# main.net
KiCad netlist of a schematic drawn in Altium Designer
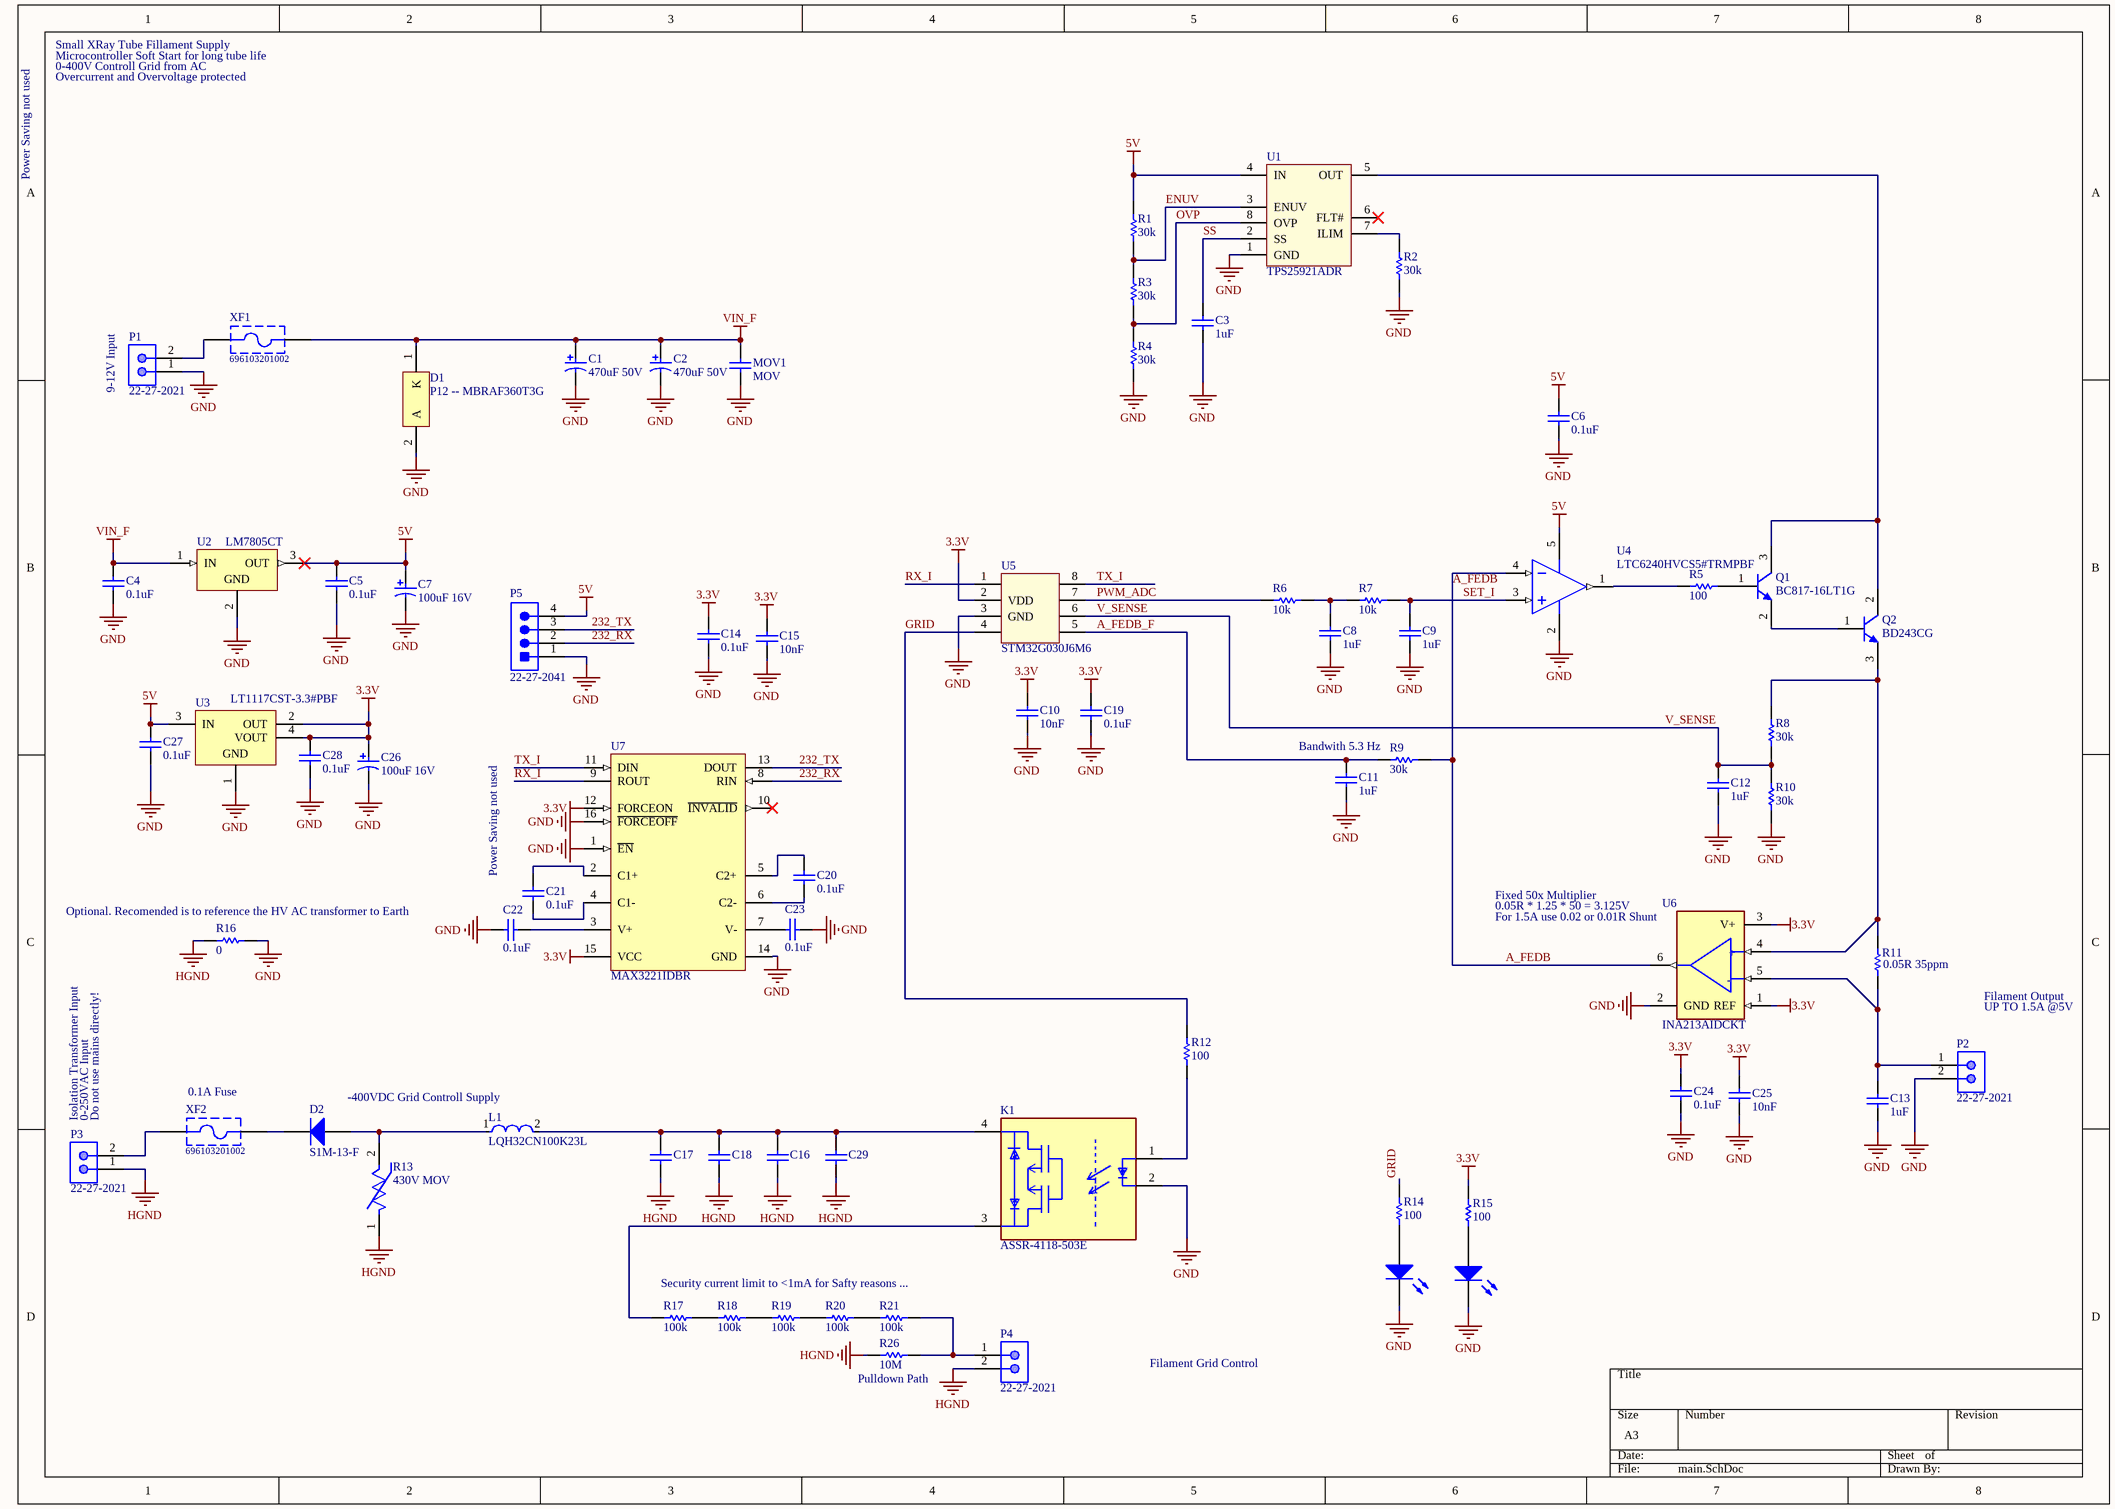
[diagram p0: main.SchDoc]

(export (version "E")
  (design (tool "Eeschema 10.0.6"))
  (components
    (comp (ref "C1")
      (value "470uF 50V")
      (footprint "PNSC-CAP-10x20-P2")
      (description "Aluminum Electrolytic Capacitor, 470 uF, +/- 20%, 50 V, -55 to 105 degC, 2-Pin THD, RoHS, Bulk")
      (fields (field (name "MANUFACTURER") "Panasonic"))
      (libsource (lib "Altium Content Vault") (part "CAP-P-2"))
    )
    (comp (ref "C2")
      (value "470uF 50V")
      (footprint "PNSC-CAP-10x20-P2")
      (description "Aluminum Electrolytic Capacitor, 470 uF, +/- 20%, 50 V, -55 to 105 degC, 2-Pin THD, RoHS, Bulk")
      (fields (field (name "MANUFACTURER") "Panasonic"))
      (libsource (lib "Altium Content Vault") (part "CAP-P-2"))
    )
    (comp (ref "C3")
      (value "1uF")
      (footprint "CAPC2013X145X50LL20T25")
      (fields (field (name "MANUFACTURER") "Kemet") (field (name "PART NUMBER") "C0805C105K4PACTU"))
      (libsource (lib "Altium Content Vault") (part "CAP"))
    )
    (comp (ref "C4")
      (value "0.1uF")
      (footprint "CAPC2013X145X50LL20T25")
      (fields (field (name "MANUFACTURER") "Kemet") (field (name "PART NUMBER") "C0805C105K4PACTU"))
      (libsource (lib "Altium Content Vault") (part "CAP"))
    )
    (comp (ref "C5")
      (value "0.1uF")
      (footprint "CAPC2013X145X50LL20T25")
      (fields (field (name "MANUFACTURER") "Kemet") (field (name "PART NUMBER") "C0805C105K4PACTU"))
      (libsource (lib "Altium Content Vault") (part "CAP"))
    )
    (comp (ref "C6")
      (value "0.1uF")
      (footprint "CAPC2013X145X50LL20T25")
      (fields (field (name "MANUFACTURER") "Kemet") (field (name "PART NUMBER") "C0805C105K4PACTU"))
      (libsource (lib "Altium Content Vault") (part "CAP"))
    )
    (comp (ref "C7")
      (value "100uF 16V")
      (footprint "CAPPR55-250-1120X630X1220")
      (fields (field (name "MANUFACTURER") "Panasonic"))
      (libsource (lib "Altium Content Vault") (part "CAP-P-2"))
    )
    (comp (ref "C8")
      (value "1uF")
      (footprint "CAPC2013X145X50LL20T25")
      (fields (field (name "MANUFACTURER") "Kemet") (field (name "PART NUMBER") "C0805C105K4PACTU"))
      (libsource (lib "Altium Content Vault") (part "CAP"))
    )
    (comp (ref "C9")
      (value "1uF")
      (footprint "CAPC2013X145X50LL20T25")
      (fields (field (name "MANUFACTURER") "Kemet") (field (name "PART NUMBER") "C0805C105K4PACTU"))
      (libsource (lib "Altium Content Vault") (part "CAP"))
    )
    (comp (ref "C10")
      (value "10nF")
      (footprint "CAPC2013X145X50LL20T25")
      (fields (field (name "MANUFACTURER") "Kemet") (field (name "PART NUMBER") "C0805C105K4PACTU"))
      (libsource (lib "Altium Content Vault") (part "CAP"))
    )
    (comp (ref "C11")
      (value "1uF")
      (footprint "CAPC2013X145X50LL20T25")
      (fields (field (name "MANUFACTURER") "Kemet") (field (name "PART NUMBER") "C0805C105K4PACTU"))
      (libsource (lib "Altium Content Vault") (part "CAP"))
    )
    (comp (ref "C12")
      (value "1uF")
      (footprint "CAPC2013X145X50LL20T25")
      (fields (field (name "MANUFACTURER") "Kemet") (field (name "PART NUMBER") "C0805C105K4PACTU"))
      (libsource (lib "Altium Content Vault") (part "CAP"))
    )
    (comp (ref "C13")
      (value "1uF")
      (footprint "CAPC2013X145X50LL20T25")
      (fields (field (name "MANUFACTURER") "Kemet") (field (name "PART NUMBER") "C0805C105K4PACTU"))
      (libsource (lib "Altium Content Vault") (part "CAP"))
    )
    (comp (ref "C14")
      (value "0.1uF")
      (footprint "CAPC2013X145X50LL20T25")
      (fields (field (name "MANUFACTURER") "Kemet") (field (name "PART NUMBER") "C0805C105K4PACTU"))
      (libsource (lib "Altium Content Vault") (part "CAP"))
    )
    (comp (ref "C15")
      (value "10nF")
      (footprint "CAPC2013X145X50LL20T25")
      (fields (field (name "MANUFACTURER") "Kemet") (field (name "PART NUMBER") "C0805C105K4PACTU"))
      (libsource (lib "Altium Content Vault") (part "CAP"))
    )
    (comp (ref "C16")
      (value "20uF 50V X7R")
      (footprint "CAPC3216X180X50LL20T30")
      (description "HighVoltaeCaps")
      (fields (field (name "MANUFACTURER") "Samsung Electro-Mechanics"))
      (libsource (lib "Altium Content Vault") (part "CAP-NP-2"))
    )
    (comp (ref "C17")
      (value "20uF 50V X7R")
      (footprint "CAPC3216X180X50LL20T30")
      (description "HighVoltaeCaps")
      (fields (field (name "MANUFACTURER") "Samsung Electro-Mechanics"))
      (libsource (lib "Altium Content Vault") (part "CAP-NP-2"))
    )
    (comp (ref "C18")
      (value "20uF 50V X7R")
      (footprint "CAPC3216X180X50LL20T30")
      (description "HighVoltaeCaps")
      (fields (field (name "MANUFACTURER") "Samsung Electro-Mechanics"))
      (libsource (lib "Altium Content Vault") (part "CAP-NP-2"))
    )
    (comp (ref "C19")
      (value "0.1uF")
      (footprint "CAPC2013X145X50LL20T25")
      (fields (field (name "MANUFACTURER") "Kemet") (field (name "PART NUMBER") "C0805C105K4PACTU"))
      (libsource (lib "Altium Content Vault") (part "CAP"))
    )
    (comp (ref "C20")
      (value "0.1uF")
      (footprint "CAPC2013X145X50LL20T25")
      (fields (field (name "MANUFACTURER") "Kemet") (field (name "PART NUMBER") "C0805C105K4PACTU"))
      (libsource (lib "Altium Content Vault") (part "CAP"))
    )
    (comp (ref "C21")
      (value "0.1uF")
      (footprint "CAPC2013X145X50LL20T25")
      (fields (field (name "MANUFACTURER") "Kemet") (field (name "PART NUMBER") "C0805C105K4PACTU"))
      (libsource (lib "Altium Content Vault") (part "CAP"))
    )
    (comp (ref "C22")
      (value "0.1uF")
      (footprint "CAPC2013X145X50LL20T25")
      (fields (field (name "MANUFACTURER") "Kemet") (field (name "PART NUMBER") "C0805C105K4PACTU"))
      (libsource (lib "Altium Content Vault") (part "CAP"))
    )
    (comp (ref "C23")
      (value "0.1uF")
      (footprint "CAPC2013X145X50LL20T25")
      (fields (field (name "MANUFACTURER") "Kemet") (field (name "PART NUMBER") "C0805C105K4PACTU"))
      (libsource (lib "Altium Content Vault") (part "CAP"))
    )
    (comp (ref "C24")
      (value "0.1uF")
      (footprint "CAPC2013X145X50LL20T25")
      (fields (field (name "MANUFACTURER") "Kemet") (field (name "PART NUMBER") "C0805C105K4PACTU"))
      (libsource (lib "Altium Content Vault") (part "CAP"))
    )
    (comp (ref "C25")
      (value "10nF")
      (footprint "CAPC2013X145X50LL20T25")
      (fields (field (name "MANUFACTURER") "Kemet") (field (name "PART NUMBER") "C0805C105K4PACTU"))
      (libsource (lib "Altium Content Vault") (part "CAP"))
    )
    (comp (ref "C26")
      (value "100uF 16V")
      (footprint "CAPPR55-250-1120X630X1220")
      (fields (field (name "MANUFACTURER") "Panasonic"))
      (libsource (lib "Altium Content Vault") (part "CAP-P-2"))
    )
    (comp (ref "C27")
      (value "0.1uF")
      (footprint "CAPC2013X145X50LL20T25")
      (fields (field (name "MANUFACTURER") "Kemet") (field (name "PART NUMBER") "C0805C105K4PACTU"))
      (libsource (lib "Altium Content Vault") (part "CAP"))
    )
    (comp (ref "C28")
      (value "0.1uF")
      (footprint "CAPC2013X145X50LL20T25")
      (fields (field (name "MANUFACTURER") "Kemet") (field (name "PART NUMBER") "C0805C105K4PACTU"))
      (libsource (lib "Altium Content Vault") (part "CAP"))
    )
    (comp (ref "C29")
      (value "20uF 50V X7R")
      (footprint "CAPC3216X180X50LL20T30")
      (description "HighVoltaeCaps")
      (fields (field (name "MANUFACTURER") "Samsung Electro-Mechanics"))
      (libsource (lib "Altium Content Vault") (part "CAP-NP-2"))
    )
    (comp (ref "D1")
      (value "P12 -- MBRAF360T3G")
      (footprint "ONSC-SMA-FL-2-403AA-01_V")
      (description "P12 -- Schottky Power Rectifier, 2-Pin SMA, Pb-Free, Tape and Reel")
      (fields (field (name "PARTNUMBER") "MBRAF360T3G") (field (name "MANUFACTURER") "On Semiconductor"))
      (libsource (lib "Altium Content Vault") (part "ONSC-D-K1A2-2_A"))
    )
    (comp (ref "D2")
      (value "S1M-13-F")
      (footprint "DIOD-S1M-13-F-SMA-2_V")
      (fields (field (name "MANUFACTURER") "Diodes Inc"))
      (libsource (lib "Altium Content Vault") (part "DIOD-D-A1K2-2"))
    )
    (comp (ref "K1")
      (value "ASSR-4118-503E")
      (footprint "FP-SO-4-MFG")
      (description "SSR RELAY SPST-NO 100MA 0-400V")
      (fields
        (field (name "OCTOPART") "https://octopart.com/assr-1218-503e-broadcom-71127361")
        (field (name "MANUFACTURER") "Broadcom")
      )
      (libsource (lib "Altium Content Vault") (part "ad51281b5d02327e8cabe319bebe261"))
    )
    (comp (ref "L1")
      (value "LQH32CN100K23L")
      (footprint "FP-LQH32CN100K23L-MFG")
      (description "FIXED IND 10UH 300MA 440 MOHM")
      (fields (field (name "TOLERANCE") "10%") (field (name "MANUFACTURER") "Murata"))
      (libsource (lib "Altium Content Vault") (part "725321dda6339637d4d059423bc1c3c"))
    )
    (comp (ref "LED1")
      (value "LED")
      (footprint "0805_A")
      (description "SMD mono-color Chip LED, WL-SMCW, Super Red")
      (fields (field (name "MANUFACTURER") "Wuerth Elektronik") (field (name "PARTNUMBER") "150080SS75000"))
      (libsource (lib "Altium Content Vault") (part "WE-LED_K1A2-2"))
    )
    (comp (ref "LED2")
      (value "LED")
      (footprint "0805_A")
      (description "SMD mono-color Chip LED, WL-SMCW, Super Red")
      (fields (field (name "MANUFACTURER") "Wuerth Elektronik") (field (name "PARTNUMBER") "150080SS75000"))
      (libsource (lib "Altium Content Vault") (part "WE-LED_K1A2-2"))
    )
    (comp (ref "MOV1")
      (value "MOV")
      (footprint "CAPC1206(3216)100_N")
      (fields (field (name "TOLERANCE") "Â±10%"))
      (libsource (lib "Altium Content Vault") (part "CAP"))
    )
    (comp (ref "P1")
      (value "22-27-2021")
      (footprint "MOLX-22-27-2021_V")
      (fields (field (name "MANUFACTURER") "Molex") (field (name "PARTNUMBER") "0022272021"))
      (libsource (lib "Altium Content Vault") (part "CN-1P-M-R2"))
    )
    (comp (ref "P2")
      (value "22-27-2021")
      (footprint "MOLX-22-27-2021_V")
      (fields (field (name "MANUFACTURER") "Molex") (field (name "PARTNUMBER") "0022272021"))
      (libsource (lib "") (part "CN-1P-M-R2_1"))
    )
    (comp (ref "P3")
      (value "22-27-2021")
      (footprint "MOLX-22-27-2021_V")
      (fields (field (name "MANUFACTURER") "Molex") (field (name "PARTNUMBER") "0022272021"))
      (libsource (lib "Altium Content Vault") (part "CN-1P-M-R2"))
    )
    (comp (ref "P4")
      (value "22-27-2021")
      (footprint "MOLX-22-27-2021_V")
      (fields (field (name "MANUFACTURER") "Molex") (field (name "PARTNUMBER") "0022272021"))
      (libsource (lib "") (part "CN-1P-M-R2_1"))
    )
    (comp (ref "P5")
      (value "22-27-2041")
      (footprint "MOLX-22-27-2041_V")
      (description "Male Header, Pitch 2.54 mm, 1 x 4 Position, Height 11.7 mm, Tail Length 3.56 mm, RoHS, Bulk")
      (fields (field (name "MANUFACTURER") "Molex"))
      (libsource (lib "Altium Content Vault") (part "CN-1P-M-R4"))
    )
    (comp (ref "Q1")
      (value "BC817-16LT1G")
      (footprint "ONSC-SOT-23-3-318-08_V")
      (description "General Purpose Transistor, NPN Silicon, 3-Pin SOT-23, Pb-Free, Tape and Reel")
      (fields (field (name "MANUFACTURER") "On Semiconductor"))
      (libsource (lib "Altium Content Vault") (part "ONSC-NPN-B1E2C3-3"))
    )
    (comp (ref "Q2")
      (value "BD243CG")
      (footprint "ONSC-TO-220-3-221A-09")
      (description "Complementary Silicon Plastic Power Transistor, 3-Pin TO-220, Pb-Free, Tube")
      (fields (field (name "MANUFACTURER") "On Semiconductor"))
      (libsource (lib "Altium Content Vault") (part "ONSC-NPN-B1C2E3-3_C"))
    )
    (comp (ref "R1")
      (value "30k")
      (footprint "RESC2013X60X40NL20T25")
      (fields (field (name "MANUFACTURER") "Panasonic") (field (name "PART NUMBER") "ERA-6AEB303V"))
      (libsource (lib "Altium Content Vault") (part "RES"))
    )
    (comp (ref "R2")
      (value "30k")
      (footprint "RESC2013X60X40NL20T25")
      (fields (field (name "MANUFACTURER") "Panasonic") (field (name "PART NUMBER") "ERA-6AEB303V"))
      (libsource (lib "Altium Content Vault") (part "RES"))
    )
    (comp (ref "R3")
      (value "30k")
      (footprint "RESC2013X60X40NL20T25")
      (fields (field (name "MANUFACTURER") "Panasonic") (field (name "PART NUMBER") "ERA-6AEB303V"))
      (libsource (lib "Altium Content Vault") (part "RES"))
    )
    (comp (ref "R4")
      (value "30k")
      (footprint "RESC2013X60X40NL20T25")
      (fields (field (name "MANUFACTURER") "Panasonic") (field (name "PART NUMBER") "ERA-6AEB303V"))
      (libsource (lib "Altium Content Vault") (part "RES"))
    )
    (comp (ref "R5")
      (value "100")
      (footprint "RESC2013X60X40NL20T25")
      (fields (field (name "MANUFACTURER") "Panasonic") (field (name "PART NUMBER") "ERA-6AEB303V"))
      (libsource (lib "Altium Content Vault") (part "RES"))
    )
    (comp (ref "R6")
      (value "10k")
      (footprint "RESC2013X60X40NL20T25")
      (fields (field (name "MANUFACTURER") "Panasonic") (field (name "PART NUMBER") "ERA-6AEB303V"))
      (libsource (lib "Altium Content Vault") (part "RES"))
    )
    (comp (ref "R7")
      (value "10k")
      (footprint "RESC2013X60X40NL20T25")
      (fields (field (name "MANUFACTURER") "Panasonic") (field (name "PART NUMBER") "ERA-6AEB303V"))
      (libsource (lib "Altium Content Vault") (part "RES"))
    )
    (comp (ref "R8")
      (value "30k")
      (footprint "RESC2013X60X40NL20T25")
      (fields (field (name "MANUFACTURER") "Panasonic") (field (name "PART NUMBER") "ERA-6AEB303V"))
      (libsource (lib "Altium Content Vault") (part "RES"))
    )
    (comp (ref "R9")
      (value "30k")
      (footprint "RESC2013X60X40NL20T25")
      (fields (field (name "MANUFACTURER") "Panasonic") (field (name "PART NUMBER") "ERA-6AEB303V"))
      (libsource (lib "Altium Content Vault") (part "RES"))
    )
    (comp (ref "R10")
      (value "30k")
      (footprint "RESC2013X60X40NL20T25")
      (fields (field (name "MANUFACTURER") "Panasonic") (field (name "PART NUMBER") "ERA-6AEB303V"))
      (libsource (lib "Altium Content Vault") (part "RES"))
    )
    (comp (ref "R11")
      (value "0.05R 35ppm")
      (footprint "RESC3216X60X45ML10T20")
      (fields (field (name "PART NUMBER") "CRCW120630R1FKEA") (field (name "MANUFACTURER") "Vishay Dale"))
      (libsource (lib "Altium Content Vault") (part "RES"))
    )
    (comp (ref "R12")
      (value "100")
      (footprint "RESC2013X60X40NL20T25")
      (fields (field (name "MANUFACTURER") "Panasonic") (field (name "PART NUMBER") "ERA-6AEB303V"))
      (libsource (lib "Altium Content Vault") (part "RES"))
    )
    (comp (ref "R13")
      (value "430V MOV")
      (footprint "FP-B72220S0-MFG")
      (description "430V MOB")
      (fields
        (field (name "MANUFACTURER") "EPCOS")
        (field (name "MANUFACTURER PART NUMBER") "B72220S0300K101")
      )
      (libsource (lib "Altium Content Vault") (part "78a88060d5b7b043d6e48adc4284376"))
    )
    (comp (ref "R14")
      (value "100")
      (footprint "RESC2013X60X40NL20T25")
      (fields (field (name "MANUFACTURER") "Panasonic") (field (name "PART NUMBER") "ERA-6AEB303V"))
      (libsource (lib "Altium Content Vault") (part "RES"))
    )
    (comp (ref "R15")
      (value "100")
      (footprint "RESC2013X60X40NL20T25")
      (fields (field (name "MANUFACTURER") "Panasonic") (field (name "PART NUMBER") "ERA-6AEB303V"))
      (libsource (lib "Altium Content Vault") (part "RES"))
    )
    (comp (ref "R16")
      (value "0")
      (footprint "RESC2013X60X40NL20T25")
      (fields (field (name "MANUFACTURER") "Panasonic") (field (name "PART NUMBER") "ERA-6AEB303V"))
      (libsource (lib "Altium Content Vault") (part "RES"))
    )
    (comp (ref "R17")
      (value "100k")
      (footprint "RESC2013X50X30NL20T20")
      (fields (field (name "MANUFACTURER") "Vishay Dale") (field (name "PART NUMBER") "CRCW0805470KFKEA"))
      (libsource (lib "Altium Content Vault") (part "RES"))
    )
    (comp (ref "R18")
      (value "100k")
      (footprint "RESC2013X50X30NL20T20")
      (fields (field (name "MANUFACTURER") "Vishay Dale") (field (name "PART NUMBER") "CRCW0805470KFKEA"))
      (libsource (lib "Altium Content Vault") (part "RES"))
    )
    (comp (ref "R19")
      (value "100k")
      (footprint "RESC2013X50X30NL20T20")
      (fields (field (name "MANUFACTURER") "Vishay Dale") (field (name "PART NUMBER") "CRCW0805470KFKEA"))
      (libsource (lib "Altium Content Vault") (part "RES"))
    )
    (comp (ref "R20")
      (value "100k")
      (footprint "RESC2013X50X30NL20T20")
      (fields (field (name "MANUFACTURER") "Vishay Dale") (field (name "PART NUMBER") "CRCW0805470KFKEA"))
      (libsource (lib "Altium Content Vault") (part "RES"))
    )
    (comp (ref "R21")
      (value "100k")
      (footprint "RESC2013X50X30NL20T20")
      (fields (field (name "MANUFACTURER") "Vishay Dale") (field (name "PART NUMBER") "CRCW0805470KFKEA"))
      (libsource (lib "Altium Content Vault") (part "RES"))
    )
    (comp (ref "R26")
      (value "10M")
      (footprint "RESC2013X50X30NL20T20")
      (fields (field (name "MANUFACTURER") "Vishay Dale") (field (name "PART NUMBER") "CRCW0805470KFKEA"))
      (libsource (lib "Altium Content Vault") (part "RES"))
    )
    (comp (ref "U1")
      (value "TPS25921ADR")
      (footprint "SOIC8")
      (description "Electronic Fuse Regulator 1.7A 8-SOIC")
      (libsource (lib "Arduino") (part "TPS25921ADR"))
    )
    (comp (ref "U2")
      (value "LM7805CT")
      (footprint "FAIR-TO-220-3")
      (description "Positive Voltage Regulator, 5 V, 1 A, -40 to 125 degC, 3-Pin TO-220, RoHS, Tube")
      (fields (field (name "MANUFACTURER") "FairchildSemiconductor"))
      (libsource (lib "Altium Content Vault") (part "FAIR-LM7805CT-TO220-3"))
    )
    (comp (ref "U3")
      (value "LT1117CST-3.3#PBF")
      (footprint "LT-ST-3-SOT-223_M")
      (fields (field (name "MANUFACTURER") "Linear Technology"))
      (libsource (lib "Altium Content Vault") (part "LT-LT1117-3_B"))
    )
    (comp (ref "U4")
      (value "LTC6240HVCS5#TRMPBF")
      (footprint "LT-S5-5-TSOT-23_N")
      (fields
        (field (name "MANUFACTURER") "Linear Technology")
        (field (name "LINEAR TECHNOLOGY PART NUMBER") "LTC6240HV")
      )
      (libsource (lib "Altium Content Vault") (part "LT-LT1395-LT18XX-LTC20XX-5"))
    )
    (comp (ref "U5")
      (value "STM32G030J6M6")
      (footprint "SOIC8")
      (libsource (lib "Arduino") (part "STM32G030J6M6"))
    )
    (comp (ref "U6")
      (value "INA213AIDCKT")
      (footprint "FP-DCK0006A-MFG")
      (description "IC CURR SENSE 1 CIRCUIT SC70-6")
      (fields
        (field (name "MANUFACTURER") "Texas Instruments")
        (field (name "OCTOPART") "https://octopart.com/ina213aidckt-texas+instruments-7767892")
      )
      (libsource (lib "Altium Content Vault") (part "9e0f38de031fe9615e73145e91d432c"))
    )
    (comp (ref "U7")
      (value "MAX3221IDBR")
      (footprint "DB0016A_L")
      (libsource (lib "Altium Content Vault") (part "TI-MAX3221-SSOP_DB-16"))
    )
    (comp (ref "XF1")
      (value "696103201002")
      (footprint "696103201002")
      (description "WR-FSH Fuse Holder Blocks Fuse Holder Blocks Clip Cover for PCB - THR Version")
      (fields (field (name "MANUFACTURER") "Wurth Elektronik") (field (name "PUBLISHER") "WurthElektronik"))
      (libsource (lib "Altium Content Vault") (part "WE-FUSE-2"))
    )
    (comp (ref "XF2")
      (value "696103201002")
      (footprint "696103201002")
      (description "WR-FSH Fuse Holder Blocks Fuse Holder Blocks Clip Cover for PCB - THR Version")
      (fields (field (name "MANUFACTURER") "Wurth Elektronik") (field (name "PUBLISHER") "WurthElektronik"))
      (libsource (lib "Altium Content Vault") (part "WE-FUSE-2"))
    )
  )
  (nets
    (net (code "1") (name "/232_RX") (class "Default")
      (node (ref "P5") (pin "2") (pinfunction "2_2") (pintype "passive"))
      (node (ref "U7") (pin "8") (pinfunction "RIN_8") (pintype "input"))
    )
    (net (code "2") (name "/232_TX") (class "Default")
      (node (ref "P5") (pin "3") (pinfunction "3_3") (pintype "passive"))
      (node (ref "U7") (pin "13") (pinfunction "DOUT_13") (pintype "tri_state"))
    )
    (net (code "3") (name "/A_FEDB") (class "Default")
      (node (ref "R9") (pin "2") (pinfunction "2_2") (pintype "passive"))
      (node (ref "U4") (pin "4") (pinfunction "-IN_4") (pintype "input"))
      (node (ref "U6") (pin "6") (pinfunction "OUT_6") (pintype "output"))
    )
    (net (code "4") (name "/A_FEDB_F") (class "Default")
      (node (ref "C11") (pin "2") (pinfunction "2_2") (pintype "passive"))
      (node (ref "R9") (pin "1") (pinfunction "1_1") (pintype "passive"))
      (node (ref "U5") (pin "5") (pinfunction "5_5") (pintype "passive"))
    )
    (net (code "5") (name "/ENUV") (class "Default")
      (node (ref "R1") (pin "2") (pinfunction "2_2") (pintype "passive"))
      (node (ref "R3") (pin "1") (pinfunction "1_1") (pintype "passive"))
      (node (ref "U1") (pin "3") (pinfunction "ENUV_3") (pintype "passive"))
    )
    (net (code "6") (name "/GRID") (class "Default")
      (node (ref "R12") (pin "1") (pinfunction "1_1") (pintype "passive"))
      (node (ref "R14") (pin "1") (pinfunction "1_1") (pintype "passive"))
      (node (ref "U5") (pin "4") (pinfunction "4_4") (pintype "passive"))
    )
    (net (code "7") (name "/OVP") (class "Default")
      (node (ref "R3") (pin "2") (pinfunction "2_2") (pintype "passive"))
      (node (ref "R4") (pin "1") (pinfunction "1_1") (pintype "passive"))
      (node (ref "U1") (pin "8") (pinfunction "OVP_8") (pintype "passive"))
    )
    (net (code "8") (name "/PWM_ADC") (class "Default")
      (node (ref "R6") (pin "2") (pinfunction "2_2") (pintype "passive"))
      (node (ref "U5") (pin "7") (pinfunction "7_7") (pintype "passive"))
    )
    (net (code "9") (name "/RX_I") (class "Default")
      (node (ref "U5") (pin "1") (pinfunction "1_1") (pintype "passive"))
      (node (ref "U7") (pin "9") (pinfunction "ROUT_9") (pintype "tri_state"))
    )
    (net (code "10") (name "/SET_I") (class "Default")
      (node (ref "C9") (pin "2") (pinfunction "2_2") (pintype "passive"))
      (node (ref "R7") (pin "1") (pinfunction "1_1") (pintype "passive"))
      (node (ref "U4") (pin "3") (pinfunction "+IN_3") (pintype "input"))
    )
    (net (code "11") (name "/SS") (class "Default")
      (node (ref "C3") (pin "2") (pinfunction "2_2") (pintype "passive"))
      (node (ref "U1") (pin "2") (pinfunction "SS_2") (pintype "passive"))
    )
    (net (code "12") (name "/TX_I") (class "Default")
      (node (ref "U5") (pin "8") (pinfunction "8_8") (pintype "passive"))
      (node (ref "U7") (pin "11") (pinfunction "DIN_11") (pintype "input"))
    )
    (net (code "13") (name "/V_SENSE") (class "Default")
      (node (ref "C12") (pin "2") (pinfunction "2_2") (pintype "passive"))
      (node (ref "R10") (pin "2") (pinfunction "2_2") (pintype "passive"))
      (node (ref "R8") (pin "1") (pinfunction "1_1") (pintype "passive"))
      (node (ref "U5") (pin "6") (pinfunction "6_6") (pintype "passive"))
    )
    (net (code "14") (name "3.3V") (class "Default")
      (node (ref "C10") (pin "2") (pinfunction "2_2") (pintype "passive"))
      (node (ref "C14") (pin "2") (pinfunction "2_2") (pintype "passive"))
      (node (ref "C15") (pin "2") (pinfunction "2_2") (pintype "passive"))
      (node (ref "C19") (pin "2") (pinfunction "2_2") (pintype "passive"))
      (node (ref "C24") (pin "2") (pinfunction "2_2") (pintype "passive"))
      (node (ref "C25") (pin "2") (pinfunction "2_2") (pintype "passive"))
      (node (ref "C26") (pin "1") (pinfunction "1_1") (pintype "passive"))
      (node (ref "C28") (pin "2") (pinfunction "2_2") (pintype "passive"))
      (node (ref "R15") (pin "1") (pinfunction "1_1") (pintype "passive"))
      (node (ref "U3") (pin "2") (pinfunction "OUT_2") (pintype "power_in"))
      (node (ref "U3") (pin "4") (pinfunction "VOUT_4") (pintype "power_in"))
      (node (ref "U5") (pin "2") (pinfunction "VDD_2") (pintype "passive"))
      (node (ref "U6") (pin "1") (pinfunction "REF_1") (pintype "input"))
      (node (ref "U6") (pin "3") (pinfunction "V+_3") (pintype "power_in"))
      (node (ref "U7") (pin "12") (pinfunction "FORCEON_12") (pintype "input"))
      (node (ref "U7") (pin "15") (pinfunction "VCC_15") (pintype "power_in"))
    )
    (net (code "15") (name "5V") (class "Default")
      (node (ref "C27") (pin "2") (pinfunction "2_2") (pintype "passive"))
      (node (ref "C5") (pin "2") (pinfunction "2_2") (pintype "passive"))
      (node (ref "C6") (pin "2") (pinfunction "2_2") (pintype "passive"))
      (node (ref "C7") (pin "1") (pinfunction "1_1") (pintype "passive"))
      (node (ref "P5") (pin "4") (pinfunction "4_4") (pintype "passive"))
      (node (ref "R1") (pin "1") (pinfunction "1_1") (pintype "passive"))
      (node (ref "U1") (pin "4") (pinfunction "IN_4") (pintype "passive"))
      (node (ref "U2") (pin "3") (pinfunction "OUT_3") (pintype "output"))
      (node (ref "U3") (pin "3") (pinfunction "IN_3") (pintype "power_in"))
      (node (ref "U4") (pin "5") (pinfunction "V+_5") (pintype "power_in"))
    )
    (net (code "16") (name "GND") (class "Default")
      (node (ref "C1") (pin "2") (pinfunction "2_2") (pintype "passive"))
      (node (ref "C10") (pin "1") (pinfunction "1_1") (pintype "passive"))
      (node (ref "C11") (pin "1") (pinfunction "1_1") (pintype "passive"))
      (node (ref "C12") (pin "1") (pinfunction "1_1") (pintype "passive"))
      (node (ref "C13") (pin "1") (pinfunction "1_1") (pintype "passive"))
      (node (ref "C14") (pin "1") (pinfunction "1_1") (pintype "passive"))
      (node (ref "C15") (pin "1") (pinfunction "1_1") (pintype "passive"))
      (node (ref "C19") (pin "1") (pinfunction "1_1") (pintype "passive"))
      (node (ref "C2") (pin "2") (pinfunction "2_2") (pintype "passive"))
      (node (ref "C22") (pin "2") (pinfunction "2_2") (pintype "passive"))
      (node (ref "C23") (pin "1") (pinfunction "1_1") (pintype "passive"))
      (node (ref "C24") (pin "1") (pinfunction "1_1") (pintype "passive"))
      (node (ref "C25") (pin "1") (pinfunction "1_1") (pintype "passive"))
      (node (ref "C26") (pin "2") (pinfunction "2_2") (pintype "passive"))
      (node (ref "C27") (pin "1") (pinfunction "1_1") (pintype "passive"))
      (node (ref "C28") (pin "1") (pinfunction "1_1") (pintype "passive"))
      (node (ref "C3") (pin "1") (pinfunction "1_1") (pintype "passive"))
      (node (ref "C4") (pin "1") (pinfunction "1_1") (pintype "passive"))
      (node (ref "C5") (pin "1") (pinfunction "1_1") (pintype "passive"))
      (node (ref "C6") (pin "1") (pinfunction "1_1") (pintype "passive"))
      (node (ref "C7") (pin "2") (pinfunction "2_2") (pintype "passive"))
      (node (ref "C8") (pin "1") (pinfunction "1_1") (pintype "passive"))
      (node (ref "C9") (pin "1") (pinfunction "1_1") (pintype "passive"))
      (node (ref "D1") (pin "2") (pinfunction "A_2") (pintype "passive"))
      (node (ref "K1") (pin "2") (pinfunction "C_2") (pintype "passive"))
      (node (ref "LED1") (pin "1") (pinfunction "K_1") (pintype "passive"))
      (node (ref "LED2") (pin "1") (pinfunction "K_1") (pintype "passive"))
      (node (ref "MOV1") (pin "1") (pinfunction "1_1") (pintype "passive"))
      (node (ref "P1") (pin "1") (pinfunction "1_1") (pintype "passive"))
      (node (ref "P2") (pin "2") (pinfunction "2_2") (pintype "passive"))
      (node (ref "P5") (pin "1") (pinfunction "1_1") (pintype "passive"))
      (node (ref "R10") (pin "1") (pinfunction "1_1") (pintype "passive"))
      (node (ref "R16") (pin "1") (pinfunction "1_1") (pintype "passive"))
      (node (ref "R2") (pin "2") (pinfunction "2_2") (pintype "passive"))
      (node (ref "R4") (pin "2") (pinfunction "2_2") (pintype "passive"))
      (node (ref "U1") (pin "1") (pinfunction "GND_1") (pintype "passive"))
      (node (ref "U2") (pin "2") (pinfunction "GND_2") (pintype "power_in"))
      (node (ref "U3") (pin "1") (pinfunction "GND_1") (pintype "power_in"))
      (node (ref "U4") (pin "2") (pinfunction "V-_2") (pintype "power_in"))
      (node (ref "U5") (pin "3") (pinfunction "GND_3") (pintype "passive"))
      (node (ref "U6") (pin "2") (pinfunction "GND_2") (pintype "power_in"))
      (node (ref "U7") (pin "1") (pinfunction "~{EN}_1") (pintype "input"))
      (node (ref "U7") (pin "14") (pinfunction "GND_14") (pintype "power_in"))
      (node (ref "U7") (pin "16") (pinfunction "~{FORCEOFF}_16") (pintype "input"))
    )
    (net (code "17") (name "HGND") (class "Default")
      (node (ref "C16") (pin "1") (pinfunction "1_1") (pintype "passive"))
      (node (ref "C17") (pin "1") (pinfunction "1_1") (pintype "passive"))
      (node (ref "C18") (pin "1") (pinfunction "1_1") (pintype "passive"))
      (node (ref "C29") (pin "1") (pinfunction "1_1") (pintype "passive"))
      (node (ref "P3") (pin "1") (pinfunction "1_1") (pintype "passive"))
      (node (ref "P4") (pin "2") (pinfunction "2_2") (pintype "passive"))
      (node (ref "R13") (pin "1") (pinfunction "1_1") (pintype "passive"))
      (node (ref "R16") (pin "2") (pinfunction "2_2") (pintype "passive"))
      (node (ref "R26") (pin "1") (pinfunction "1_1") (pintype "passive"))
    )
    (net (code "18") (name "Net-(C8-Pad2)") (class "Default")
      (node (ref "C8") (pin "2") (pinfunction "2_2") (pintype "passive"))
      (node (ref "R6") (pin "1") (pinfunction "1_1") (pintype "passive"))
      (node (ref "R7") (pin "2") (pinfunction "2_2") (pintype "passive"))
    )
    (net (code "19") (name "Net-(D2-A)") (class "Default")
      (node (ref "D2") (pin "1") (pinfunction "A_1") (pintype "passive"))
      (node (ref "L1") (pin "1") (pinfunction "1_1") (pintype "passive"))
      (node (ref "R13") (pin "2") (pinfunction "2_2") (pintype "passive"))
    )
    (net (code "20") (name "Net-(D2-K)") (class "Default")
      (node (ref "D2") (pin "2") (pinfunction "K_2") (pintype "passive"))
      (node (ref "XF2") (pin "2") (pinfunction "2_2") (pintype "passive"))
    )
    (net (code "21") (name "Net-(K1-1_DRAIN)") (class "Default")
      (node (ref "K1") (pin "3") (pinfunction "1_DRAIN_3") (pintype "passive"))
      (node (ref "R17") (pin "1") (pinfunction "1_1") (pintype "passive"))
    )
    (net (code "22") (name "Net-(K1-2_DRAIN)") (class "Default")
      (node (ref "C16") (pin "2") (pinfunction "2_2") (pintype "passive"))
      (node (ref "C17") (pin "2") (pinfunction "2_2") (pintype "passive"))
      (node (ref "C18") (pin "2") (pinfunction "2_2") (pintype "passive"))
      (node (ref "C29") (pin "2") (pinfunction "2_2") (pintype "passive"))
      (node (ref "K1") (pin "4") (pinfunction "2_DRAIN_4") (pintype "passive"))
      (node (ref "L1") (pin "2") (pinfunction "2_2") (pintype "passive"))
    )
    (net (code "23") (name "Net-(K1-A)") (class "Default")
      (node (ref "K1") (pin "1") (pinfunction "A_1") (pintype "passive"))
      (node (ref "R12") (pin "2") (pinfunction "2_2") (pintype "passive"))
    )
    (net (code "24") (name "Net-(LED1-A)") (class "Default")
      (node (ref "LED1") (pin "2") (pinfunction "A_2") (pintype "passive"))
      (node (ref "R14") (pin "2") (pinfunction "2_2") (pintype "passive"))
    )
    (net (code "25") (name "Net-(LED2-A)") (class "Default")
      (node (ref "LED2") (pin "2") (pinfunction "A_2") (pintype "passive"))
      (node (ref "R15") (pin "2") (pinfunction "2_2") (pintype "passive"))
    )
    (net (code "26") (name "Net-(P1-Pad2)") (class "Default")
      (node (ref "P1") (pin "2") (pinfunction "2_2") (pintype "passive"))
      (node (ref "XF1") (pin "1") (pinfunction "1_1") (pintype "passive"))
    )
    (net (code "27") (name "Net-(P3-Pad2)") (class "Default")
      (node (ref "P3") (pin "2") (pinfunction "2_2") (pintype "passive"))
      (node (ref "XF2") (pin "1") (pinfunction "1_1") (pintype "passive"))
    )
    (net (code "28") (name "Net-(P4-Pad1)") (class "Default")
      (node (ref "P4") (pin "1") (pinfunction "1_1") (pintype "passive"))
      (node (ref "R21") (pin "2") (pinfunction "2_2") (pintype "passive"))
      (node (ref "R26") (pin "2") (pinfunction "2_2") (pintype "passive"))
    )
    (net (code "29") (name "Net-(Q1-B)") (class "Default")
      (node (ref "Q1") (pin "1") (pinfunction "B_1") (pintype "passive"))
      (node (ref "R5") (pin "1") (pinfunction "1_1") (pintype "passive"))
    )
    (net (code "30") (name "Net-(Q1-C)") (class "Default")
      (node (ref "Q1") (pin "3") (pinfunction "C_3") (pintype "passive"))
      (node (ref "Q2") (pin "2") (pinfunction "C_2") (pintype "passive"))
      (node (ref "U1") (pin "5") (pinfunction "OUT_5") (pintype "passive"))
    )
    (net (code "31") (name "Net-(Q1-E)") (class "Default")
      (node (ref "Q1") (pin "2") (pinfunction "E_2") (pintype "passive"))
      (node (ref "Q2") (pin "1") (pinfunction "B_1") (pintype "passive"))
    )
    (net (code "32") (name "Net-(Q2-E)") (class "Default")
      (node (ref "Q2") (pin "3") (pinfunction "E_3") (pintype "passive"))
      (node (ref "R11") (pin "2") (pinfunction "2_2") (pintype "passive"))
      (node (ref "R8") (pin "2") (pinfunction "2_2") (pintype "passive"))
      (node (ref "U6") (pin "4") (pinfunction "IN+_4") (pintype "input"))
    )
    (net (code "33") (name "Net-(R17-Pad2)") (class "Default")
      (node (ref "R17") (pin "2") (pinfunction "2_2") (pintype "passive"))
      (node (ref "R18") (pin "1") (pinfunction "1_1") (pintype "passive"))
    )
    (net (code "34") (name "Net-(R18-Pad2)") (class "Default")
      (node (ref "R18") (pin "2") (pinfunction "2_2") (pintype "passive"))
      (node (ref "R19") (pin "1") (pinfunction "1_1") (pintype "passive"))
    )
    (net (code "35") (name "Net-(R19-Pad2)") (class "Default")
      (node (ref "R19") (pin "2") (pinfunction "2_2") (pintype "passive"))
      (node (ref "R20") (pin "1") (pinfunction "1_1") (pintype "passive"))
    )
    (net (code "36") (name "Net-(R20-Pad2)") (class "Default")
      (node (ref "R20") (pin "2") (pinfunction "2_2") (pintype "passive"))
      (node (ref "R21") (pin "1") (pinfunction "1_1") (pintype "passive"))
    )
    (net (code "37") (name "Net-(U1-ILIM)") (class "Default")
      (node (ref "R2") (pin "1") (pinfunction "1_1") (pintype "passive"))
      (node (ref "U1") (pin "7") (pinfunction "ILIM_7") (pintype "passive"))
    )
    (net (code "38") (name "Net-(U4-OUT)") (class "Default")
      (node (ref "R5") (pin "2") (pinfunction "2_2") (pintype "passive"))
      (node (ref "U4") (pin "1") (pinfunction "OUT_1") (pintype "output"))
    )
    (net (code "39") (name "Net-(U6-IN-)") (class "Default")
      (node (ref "C13") (pin "2") (pinfunction "2_2") (pintype "passive"))
      (node (ref "P2") (pin "1") (pinfunction "1_1") (pintype "passive"))
      (node (ref "R11") (pin "1") (pinfunction "1_1") (pintype "passive"))
      (node (ref "U6") (pin "5") (pinfunction "IN-_5") (pintype "input"))
    )
    (net (code "40") (name "Net-(U7-C1+)") (class "Default")
      (node (ref "C21") (pin "2") (pinfunction "2_2") (pintype "passive"))
      (node (ref "U7") (pin "2") (pinfunction "C1+_2") (pintype "passive"))
    )
    (net (code "41") (name "Net-(U7-C1-)") (class "Default")
      (node (ref "C21") (pin "1") (pinfunction "1_1") (pintype "passive"))
      (node (ref "U7") (pin "4") (pinfunction "C1-_4") (pintype "passive"))
    )
    (net (code "42") (name "Net-(U7-C2+)") (class "Default")
      (node (ref "C20") (pin "2") (pinfunction "2_2") (pintype "passive"))
      (node (ref "U7") (pin "5") (pinfunction "C2+_5") (pintype "passive"))
    )
    (net (code "43") (name "Net-(U7-C2-)") (class "Default")
      (node (ref "C20") (pin "1") (pinfunction "1_1") (pintype "passive"))
      (node (ref "U7") (pin "6") (pinfunction "C2-_6") (pintype "passive"))
    )
    (net (code "44") (name "Net-(U7-V+)") (class "Default")
      (node (ref "C22") (pin "1") (pinfunction "1_1") (pintype "passive"))
      (node (ref "U7") (pin "3") (pinfunction "V+_3") (pintype "power_in"))
    )
    (net (code "45") (name "Net-(U7-V-)") (class "Default")
      (node (ref "C23") (pin "2") (pinfunction "2_2") (pintype "passive"))
      (node (ref "U7") (pin "7") (pinfunction "V-_7") (pintype "power_in"))
    )
    (net (code "46") (name "VIN_F") (class "Default")
      (node (ref "C1") (pin "1") (pinfunction "1_1") (pintype "passive"))
      (node (ref "C2") (pin "1") (pinfunction "1_1") (pintype "passive"))
      (node (ref "C4") (pin "2") (pinfunction "2_2") (pintype "passive"))
      (node (ref "D1") (pin "1") (pinfunction "K_1") (pintype "passive"))
      (node (ref "MOV1") (pin "2") (pinfunction "2_2") (pintype "passive"))
      (node (ref "U2") (pin "1") (pinfunction "IN_1") (pintype "input"))
      (node (ref "XF1") (pin "2") (pinfunction "2_2") (pintype "passive"))
    )
    (net (code "47") (name "unconnected-(U1-FLT#-Pad6)") (class "Default")
      (node (ref "U1") (pin "6") (pinfunction "FLT#_6") (pintype "passive+no_connect"))
    )
    (net (code "48") (name "unconnected-(U7-~{INVALID}-Pad10)") (class "Default")
      (node (ref "U7") (pin "10") (pinfunction "~{INVALID}_10") (pintype "output+no_connect"))
    )
  )
)
